# KeyBoy.net
KiCad netlist of a schematic drawn in EAGLE
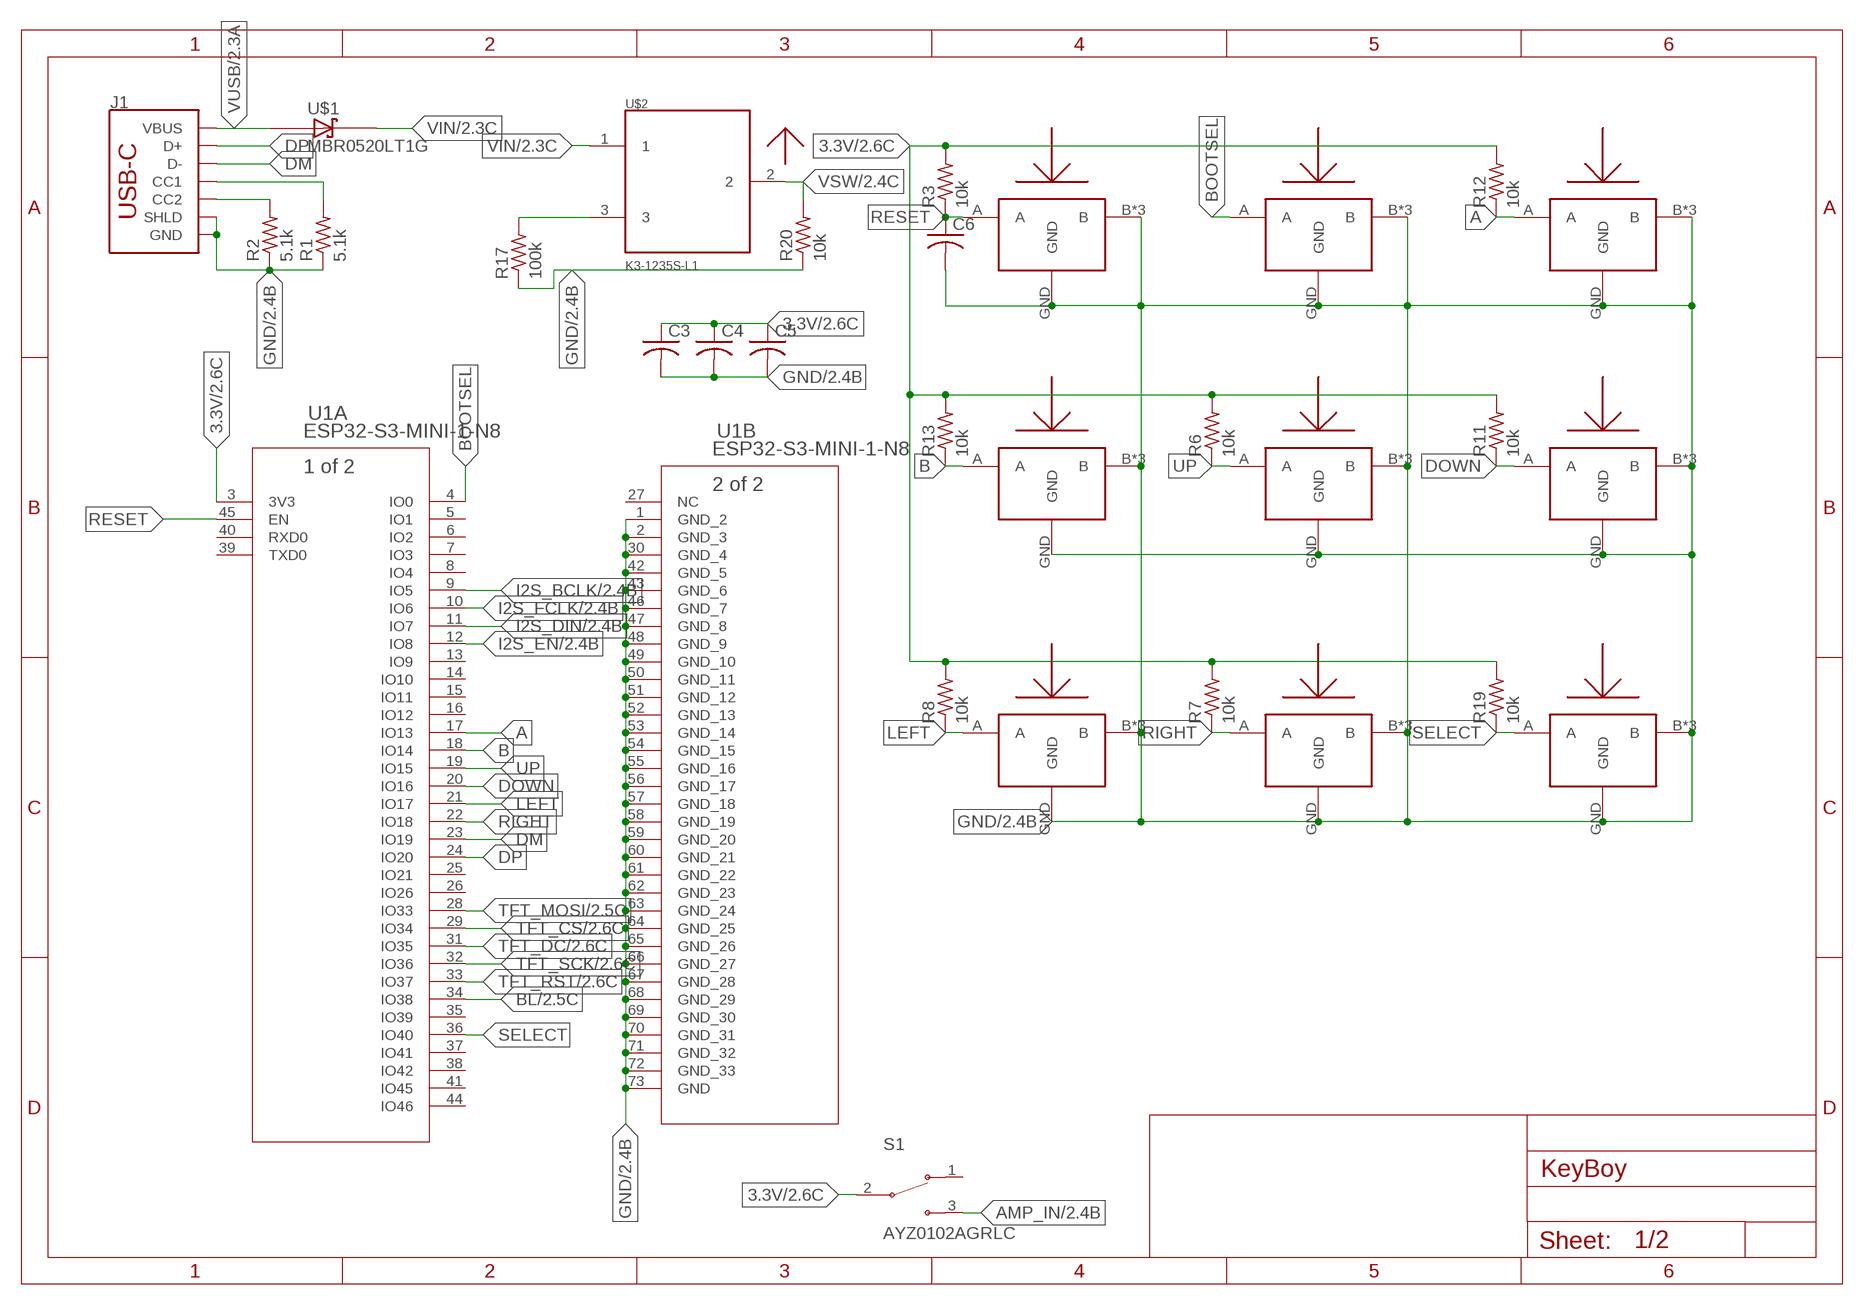
[diagram p0: schematic, sheet 1]
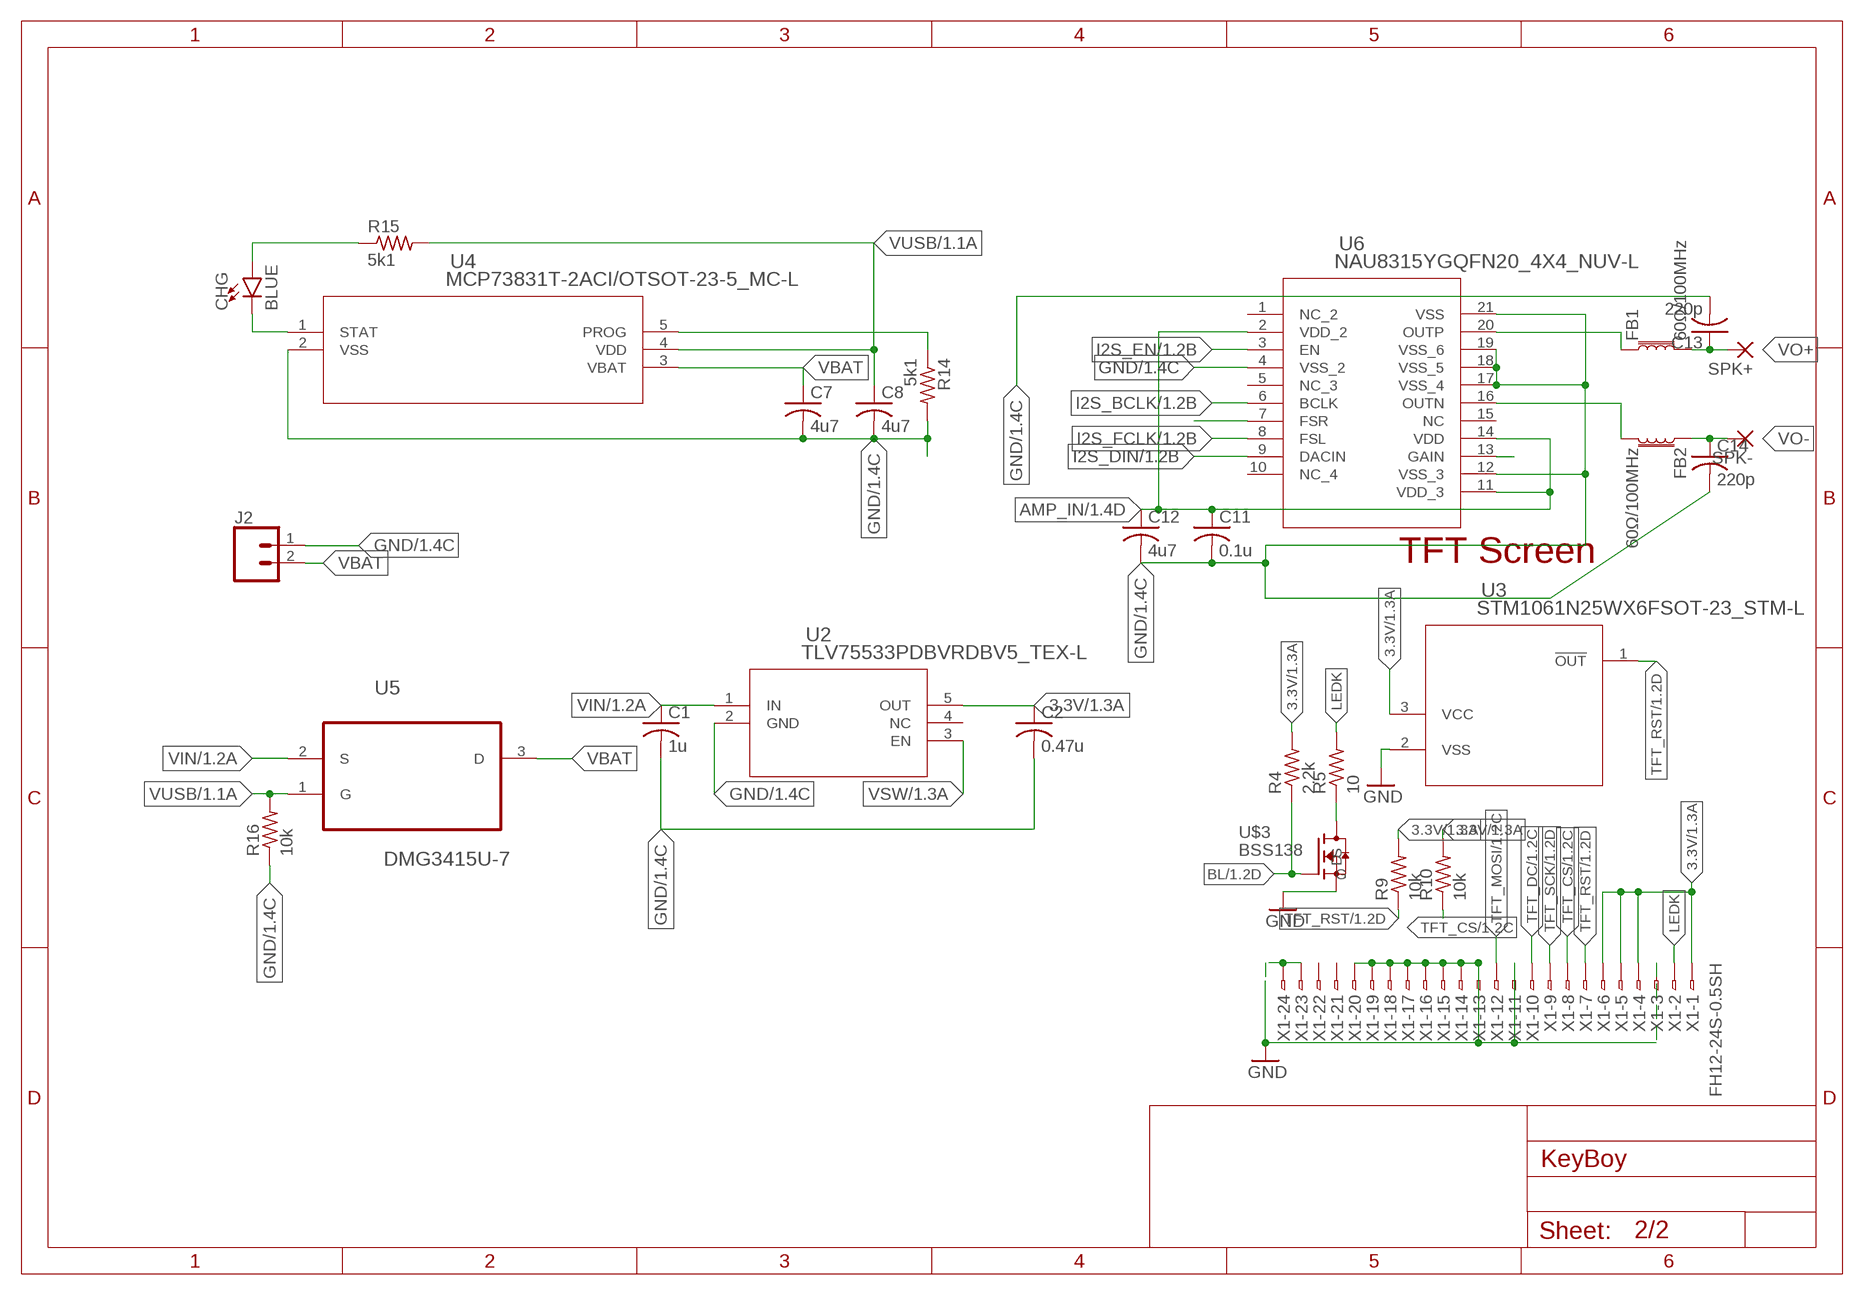
[diagram p1: schematic, sheet 2]

(export (version "E")
  (design (tool "Eeschema 10.0.6"))
  (components
    (comp (ref "C1")
      (value "1u")
      (footprint "eagle-import:C0402")
      (libsource (lib "eagle-import") (part "C-USC0402"))
    )
    (comp (ref "C2")
      (value "0.47u")
      (footprint "eagle-import:C0402")
      (libsource (lib "eagle-import") (part "C-USC0402"))
    )
    (comp (ref "C7")
      (value "4u7")
      (footprint "eagle-import:C0603")
      (libsource (lib "eagle-import") (part "C-USC0603"))
    )
    (comp (ref "C8")
      (value "4u7")
      (footprint "eagle-import:C0603")
      (libsource (lib "eagle-import") (part "C-USC0603"))
    )
    (comp (ref "C11")
      (value "0.1u")
      (footprint "eagle-import:C0603")
      (libsource (lib "eagle-import") (part "C-USC0603"))
    )
    (comp (ref "C12")
      (value "4u7")
      (footprint "eagle-import:C0603")
      (libsource (lib "eagle-import") (part "C-USC0603"))
    )
    (comp (ref "C13")
      (value "220p")
      (footprint "eagle-import:C0603")
      (libsource (lib "eagle-import") (part "C-USC0603"))
    )
    (comp (ref "C14")
      (value "220p")
      (footprint "eagle-import:C0603")
      (libsource (lib "eagle-import") (part "C-USC0603"))
    )
    (comp (ref "CHG")
      (value "BLUE")
      (footprint "eagle-import:LED-0603")
      (libsource (lib "eagle-import") (part "LED0603"))
    )
    (comp (ref "FB1")
      (value "60Ω/100MHz")
      (footprint "eagle-import:0603")
      (libsource (lib "eagle-import") (part "FERRITE_BEAD-0603"))
    )
    (comp (ref "FB2")
      (value "60Ω/100MHz")
      (footprint "eagle-import:0603")
      (libsource (lib "eagle-import") (part "FERRITE_BEAD-0603"))
    )
    (comp (ref "J2")
      (value "CONN_02-JST-2MM-SMT")
      (footprint "eagle-import:JST-2-SMD")
      (libsource (lib "eagle-import") (part "CONN_02-JST-2MM-SMT"))
    )
    (comp (ref "R4")
      (value "2.2k")
      (footprint "eagle-import:R0603")
      (libsource (lib "eagle-import") (part "R-US_R0603"))
    )
    (comp (ref "R5")
      (value "10")
      (footprint "eagle-import:R0402")
      (libsource (lib "eagle-import") (part "R-US_R0402"))
    )
    (comp (ref "R9")
      (value "10k")
      (footprint "eagle-import:R0402")
      (libsource (lib "eagle-import") (part "R-US_R0402"))
    )
    (comp (ref "R10")
      (value "10k")
      (footprint "eagle-import:R0402")
      (libsource (lib "eagle-import") (part "R-US_R0402"))
    )
    (comp (ref "R14")
      (value "5k1")
      (footprint "eagle-import:R0603")
      (libsource (lib "eagle-import") (part "R-US_R0603"))
    )
    (comp (ref "R15")
      (value "5k1")
      (footprint "eagle-import:R0603")
      (libsource (lib "eagle-import") (part "R-US_R0603"))
    )
    (comp (ref "R16")
      (value "10k")
      (footprint "eagle-import:R0402")
      (libsource (lib "eagle-import") (part "R-US_R0402"))
    )
    (comp (ref "SPK+")
      (value "SMD5")
      (footprint "eagle-import:SMD2,54-5,08")
      (libsource (lib "eagle-import") (part "SMD5"))
    )
    (comp (ref "SPK-")
      (value "SMD5")
      (footprint "eagle-import:SMD2,54-5,08")
      (libsource (lib "eagle-import") (part "SMD5"))
    )
    (comp (ref "U$3")
      (value "BSS138")
      (footprint "eagle-import:BSS138")
      (fields (field (name "MF") "MICROSS/On Semiconductor"))
      (libsource (lib "eagle-import") (part "BSS138"))
    )
    (comp (ref "U2")
      (value "TLV75533PDBVRDBV5_TEX-L")
      (footprint "eagle-import:DBV5_TEX-L")
      (fields
        (field (name "MANUFACTURER_PART_NUMBER") "TLV75533PDBVR")
        (field (name "COPYRIGHT") "Copyright (C) 2018 Accelerated Designs. All rights reserved")
      )
      (libsource (lib "eagle-import") (part "TLV75533PDBVRDBV5_TEX-L"))
    )
    (comp (ref "U3")
      (value "STM1061N25WX6FSOT-23_STM-L")
      (footprint "eagle-import:SOT-23_STM-L")
      (fields
        (field (name "MANUFACTURER_PART_NUMBER") "STM1061N25WX6F")
        (field (name "COPYRIGHT") "Copyright (C) 2021 Ultra Librarian. All rights reserved.")
      )
      (libsource (lib "eagle-import") (part "STM1061N25WX6FSOT-23_STM-L"))
    )
    (comp (ref "U4")
      (value "MCP73831T-2ACI/OTSOT-23-5_MC-L")
      (footprint "eagle-import:SOT-23-5_MC-L")
      (fields (field (name "MANUFACTURER_PART_NUMBER") "MCP73831T-2ACI/OT"))
      (libsource (lib "eagle-import") (part "MCP73831T-2ACI/OTSOT-23-5_MC-L"))
    )
    (comp (ref "U5")
      (value "DMG3415U-7")
      (footprint "eagle-import:SOT95P240X105-3N")
      (fields (field (name "MF") "Diodes Inc."))
      (libsource (lib "eagle-import") (part "DMG3415U-7"))
    )
    (comp (ref "U6")
      (value "NAU8315YGQFN20_4X4_NUV-L")
      (footprint "eagle-import:QFN20_4X4_NUV-L")
      (fields
        (field (name "MANUFACTURER_PART_NUMBER") "NAU8315YG")
        (field (name "COPYRIGHT") "Copyright (C) 2023 Ultra Librarian. All rights reserved.")
      )
      (libsource (lib "eagle-import") (part "NAU8315YGQFN20_4X4_NUV-L"))
    )
    (comp (ref "X1")
      (value "FH12-24S-0.5SH")
      (footprint "eagle-import:FH12-24S-0.5SH")
      (fields (field (name "MPN") "FH12-24S-0.5SH(55)"))
      (libsource (lib "eagle-import") (part "FH12-24S-0.5SH"))
    )
    (comp (ref "A")
      (value "SOF-232HST")
      (footprint "eagle-import:3.3X2.9")
      (libsource (lib "eagle-import") (part "SOF-232HST"))
    )
    (comp (ref "B")
      (value "SOF-232HST")
      (footprint "eagle-import:3.3X2.9")
      (libsource (lib "eagle-import") (part "SOF-232HST"))
    )
    (comp (ref "BOOTSEL")
      (value "SOF-232HST")
      (footprint "eagle-import:3.3X2.9")
      (libsource (lib "eagle-import") (part "SOF-232HST"))
    )
    (comp (ref "C3")
      (value "C-USC0402")
      (footprint "eagle-import:C0402")
      (libsource (lib "eagle-import") (part "C-USC0402"))
    )
    (comp (ref "C4")
      (value "C-USC0402")
      (footprint "eagle-import:C0402")
      (libsource (lib "eagle-import") (part "C-USC0402"))
    )
    (comp (ref "C5")
      (value "C-USC0402")
      (footprint "eagle-import:C0402")
      (libsource (lib "eagle-import") (part "C-USC0402"))
    )
    (comp (ref "C6")
      (value "C-USC0402")
      (footprint "eagle-import:C0402")
      (libsource (lib "eagle-import") (part "C-USC0402"))
    )
    (comp (ref "DOWN")
      (value "SOF-232HST")
      (footprint "eagle-import:3.3X2.9")
      (libsource (lib "eagle-import") (part "SOF-232HST"))
    )
    (comp (ref "J1")
      (value "USB_C_2-LAYER_PADS")
      (footprint "eagle-import:USB-C-16P-2LAYER-PADS")
      (libsource (lib "eagle-import") (part "USB_C_2-LAYER_PADS"))
    )
    (comp (ref "LEFT")
      (value "SOF-232HST")
      (footprint "eagle-import:3.3X2.9")
      (libsource (lib "eagle-import") (part "SOF-232HST"))
    )
    (comp (ref "R1")
      (value "5.1k")
      (footprint "eagle-import:R0402")
      (libsource (lib "eagle-import") (part "R-US_R0402"))
    )
    (comp (ref "R2")
      (value "5.1k")
      (footprint "eagle-import:R0402")
      (libsource (lib "eagle-import") (part "R-US_R0402"))
    )
    (comp (ref "R3")
      (value "10k")
      (footprint "eagle-import:R0402")
      (libsource (lib "eagle-import") (part "R-US_R0402"))
    )
    (comp (ref "R6")
      (value "10k")
      (footprint "eagle-import:R0402")
      (libsource (lib "eagle-import") (part "R-US_R0402"))
    )
    (comp (ref "R7")
      (value "10k")
      (footprint "eagle-import:R0402")
      (libsource (lib "eagle-import") (part "R-US_R0402"))
    )
    (comp (ref "R8")
      (value "10k")
      (footprint "eagle-import:R0402")
      (libsource (lib "eagle-import") (part "R-US_R0402"))
    )
    (comp (ref "R11")
      (value "10k")
      (footprint "eagle-import:R0402")
      (libsource (lib "eagle-import") (part "R-US_R0402"))
    )
    (comp (ref "R12")
      (value "10k")
      (footprint "eagle-import:R0402")
      (libsource (lib "eagle-import") (part "R-US_R0402"))
    )
    (comp (ref "R13")
      (value "10k")
      (footprint "eagle-import:R0402")
      (libsource (lib "eagle-import") (part "R-US_R0402"))
    )
    (comp (ref "R17")
      (value "100k")
      (footprint "eagle-import:R0402")
      (libsource (lib "eagle-import") (part "R-US_R0402"))
    )
    (comp (ref "R19")
      (value "10k")
      (footprint "eagle-import:R0402")
      (libsource (lib "eagle-import") (part "R-US_R0402"))
    )
    (comp (ref "R20")
      (value "10k")
      (footprint "eagle-import:R0402")
      (libsource (lib "eagle-import") (part "R-US_R0402"))
    )
    (comp (ref "RESET")
      (value "SOF-232HST")
      (footprint "eagle-import:3.3X2.9")
      (libsource (lib "eagle-import") (part "SOF-232HST"))
    )
    (comp (ref "RIGHT")
      (value "SOF-232HST")
      (footprint "eagle-import:3.3X2.9")
      (libsource (lib "eagle-import") (part "SOF-232HST"))
    )
    (comp (ref "S1")
      (value "AYZ0102AGRLC")
      (footprint "eagle-import:SW_AYZ0102AGRLC")
      (fields (field (name "MF") "C&K"))
      (libsource (lib "eagle-import") (part "AYZ0102AGRLC"))
    )
    (comp (ref "SELECT")
      (value "SOF-232HST")
      (footprint "eagle-import:3.3X2.9")
      (libsource (lib "eagle-import") (part "SOF-232HST"))
    )
    (comp (ref "U$1")
      (value "MBR0520LT1G")
      (footprint "eagle-import:SOD3716X117(SOD-123)")
      (fields (field (name "MF") "ON Semiconductor"))
      (libsource (lib "eagle-import") (part "MBR0520LT1G"))
    )
    (comp (ref "U$2")
      (value "K3-1235S-L1")
      (footprint "eagle-import:K3-1235S-L1")
      (libsource (lib "eagle-import") (part "K3-1235S-L1"))
    )
    (comp (ref "U1")
      (value "ESP32-S3-MINI-1-N8")
      (footprint "eagle-import:ESP32-S2-MINI-1-N4_EXP")
      (fields
        (field (name "MANUFACTURER_PART_NUMBER") "ESP32-S2-MINI-1-N4")
        (field (name "COPYRIGHT") "Copyright (C) 2021 Ultra Librarian. All rights reserved.")
      )
      (libsource (lib "eagle-import") (part "ESP32-S2-MINI-1-N4"))
    )
    (comp (ref "UP")
      (value "SOF-232HST")
      (footprint "eagle-import:3.3X2.9")
      (libsource (lib "eagle-import") (part "SOF-232HST"))
    )
  )
  (nets
    (net (code "1") (name "3.3V") (class "Default")
      (node (ref "C2") (pin "1") (pinfunction "1_1") (pintype "passive"))
      (node (ref "C3") (pin "1") (pinfunction "1_1") (pintype "passive"))
      (node (ref "C4") (pin "1") (pinfunction "1_1") (pintype "passive"))
      (node (ref "C5") (pin "1") (pinfunction "1_1") (pintype "passive"))
      (node (ref "R10") (pin "2") (pinfunction "2_2") (pintype "passive"))
      (node (ref "R11") (pin "2") (pinfunction "2_2") (pintype "passive"))
      (node (ref "R12") (pin "2") (pinfunction "2_2") (pintype "passive"))
      (node (ref "R13") (pin "2") (pinfunction "2_2") (pintype "passive"))
      (node (ref "R19") (pin "2") (pinfunction "2_2") (pintype "passive"))
      (node (ref "R3") (pin "2") (pinfunction "2_2") (pintype "passive"))
      (node (ref "R4") (pin "2") (pinfunction "2_2") (pintype "passive"))
      (node (ref "R6") (pin "2") (pinfunction "2_2") (pintype "passive"))
      (node (ref "R7") (pin "2") (pinfunction "2_2") (pintype "passive"))
      (node (ref "R8") (pin "2") (pinfunction "2_2") (pintype "passive"))
      (node (ref "R9") (pin "2") (pinfunction "2_2") (pintype "passive"))
      (node (ref "S1") (pin "2") (pinfunction "2_2") (pintype "passive"))
      (node (ref "U1") (pin "3") (pinfunction "3V3_3") (pintype "passive"))
      (node (ref "U2") (pin "5") (pinfunction "OUT_5") (pintype "output"))
      (node (ref "U3") (pin "3") (pinfunction "VCC_3") (pintype "power_in"))
      (node (ref "X1") (pin "1") (pinfunction "1_1") (pintype "passive"))
      (node (ref "X1") (pin "4") (pinfunction "1_4") (pintype "passive"))
      (node (ref "X1") (pin "5") (pinfunction "1_5") (pintype "passive"))
      (node (ref "X1") (pin "6") (pinfunction "1_6") (pintype "passive"))
    )
    (net (code "2") (name "A") (class "Default")
      (node (ref "A") (pin "A") (pinfunction "A_A") (pintype "bidirectional"))
      (node (ref "R12") (pin "1") (pinfunction "1_1") (pintype "passive"))
      (node (ref "U1") (pin "17") (pinfunction "IO13_17") (pintype "bidirectional"))
    )
    (net (code "3") (name "AMP_IN") (class "Default")
      (node (ref "C11") (pin "1") (pinfunction "1_1") (pintype "passive"))
      (node (ref "C12") (pin "1") (pinfunction "1_1") (pintype "passive"))
      (node (ref "S1") (pin "3") (pinfunction "3_3") (pintype "passive"))
      (node (ref "U6") (pin "11") (pinfunction "VDD_3_11") (pintype "power_in"))
      (node (ref "U6") (pin "14") (pinfunction "VDD_14") (pintype "power_in"))
      (node (ref "U6") (pin "2") (pinfunction "VDD_2_2") (pintype "power_in"))
    )
    (net (code "4") (name "B") (class "Default")
      (node (ref "B") (pin "A") (pinfunction "A_A") (pintype "bidirectional"))
      (node (ref "R13") (pin "1") (pinfunction "1_1") (pintype "passive"))
      (node (ref "U1") (pin "18") (pinfunction "IO14_18") (pintype "bidirectional"))
    )
    (net (code "5") (name "BL") (class "Default")
      (node (ref "R4") (pin "1") (pinfunction "1_1") (pintype "passive"))
      (node (ref "U$3") (pin "G") (pinfunction "G_G") (pintype "passive"))
      (node (ref "U1") (pin "34") (pinfunction "IO38_34") (pintype "bidirectional"))
    )
    (net (code "6") (name "BOOTSEL") (class "Default")
      (node (ref "BOOTSEL") (pin "A") (pinfunction "A_A") (pintype "bidirectional"))
      (node (ref "U1") (pin "4") (pinfunction "IO0_4") (pintype "bidirectional"))
    )
    (net (code "7") (name "DM") (class "Default")
      (node (ref "J1") (pin "A7") (pinfunction "D-_A7") (pintype "bidirectional"))
      (node (ref "J1") (pin "B7") (pinfunction "D-_B7") (pintype "bidirectional"))
      (node (ref "U1") (pin "23") (pinfunction "IO19_23") (pintype "bidirectional"))
    )
    (net (code "8") (name "DOWN") (class "Default")
      (node (ref "DOWN") (pin "A") (pinfunction "A_A") (pintype "bidirectional"))
      (node (ref "R11") (pin "1") (pinfunction "1_1") (pintype "passive"))
      (node (ref "U1") (pin "20") (pinfunction "IO16_20") (pintype "bidirectional"))
    )
    (net (code "9") (name "DP") (class "Default")
      (node (ref "J1") (pin "A6") (pinfunction "D+_A6") (pintype "bidirectional"))
      (node (ref "J1") (pin "B6") (pinfunction "D+_B6") (pintype "bidirectional"))
      (node (ref "U1") (pin "24") (pinfunction "IO20_24") (pintype "bidirectional"))
    )
    (net (code "10") (name "GND") (class "Default")
      (node (ref "A") (pin "B") (pinfunction "B_B") (pintype "bidirectional"))
      (node (ref "A") (pin "B2") (pinfunction "B_B2") (pintype "bidirectional"))
      (node (ref "A") (pin "B3") (pinfunction "B_B3") (pintype "bidirectional"))
      (node (ref "A") (pin "GND") (pinfunction "GND_GND") (pintype "bidirectional"))
      (node (ref "B") (pin "B") (pinfunction "B_B") (pintype "bidirectional"))
      (node (ref "B") (pin "B2") (pinfunction "B_B2") (pintype "bidirectional"))
      (node (ref "B") (pin "B3") (pinfunction "B_B3") (pintype "bidirectional"))
      (node (ref "B") (pin "GND") (pinfunction "GND_GND") (pintype "bidirectional"))
      (node (ref "BOOTSEL") (pin "B") (pinfunction "B_B") (pintype "bidirectional"))
      (node (ref "BOOTSEL") (pin "B2") (pinfunction "B_B2") (pintype "bidirectional"))
      (node (ref "BOOTSEL") (pin "B3") (pinfunction "B_B3") (pintype "bidirectional"))
      (node (ref "BOOTSEL") (pin "GND") (pinfunction "GND_GND") (pintype "bidirectional"))
      (node (ref "C1") (pin "2") (pinfunction "2_2") (pintype "passive"))
      (node (ref "C11") (pin "2") (pinfunction "2_2") (pintype "passive"))
      (node (ref "C12") (pin "2") (pinfunction "2_2") (pintype "passive"))
      (node (ref "C13") (pin "2") (pinfunction "2_2") (pintype "passive"))
      (node (ref "C14") (pin "2") (pinfunction "2_2") (pintype "passive"))
      (node (ref "C2") (pin "2") (pinfunction "2_2") (pintype "passive"))
      (node (ref "C3") (pin "2") (pinfunction "2_2") (pintype "passive"))
      (node (ref "C4") (pin "2") (pinfunction "2_2") (pintype "passive"))
      (node (ref "C5") (pin "2") (pinfunction "2_2") (pintype "passive"))
      (node (ref "C6") (pin "2") (pinfunction "2_2") (pintype "passive"))
      (node (ref "C7") (pin "2") (pinfunction "2_2") (pintype "passive"))
      (node (ref "C8") (pin "2") (pinfunction "2_2") (pintype "passive"))
      (node (ref "DOWN") (pin "B") (pinfunction "B_B") (pintype "bidirectional"))
      (node (ref "DOWN") (pin "B2") (pinfunction "B_B2") (pintype "bidirectional"))
      (node (ref "DOWN") (pin "B3") (pinfunction "B_B3") (pintype "bidirectional"))
      (node (ref "DOWN") (pin "GND") (pinfunction "GND_GND") (pintype "bidirectional"))
      (node (ref "J1") (pin "GND") (pinfunction "GND_GND") (pintype "bidirectional"))
      (node (ref "J1") (pin "GND2") (pinfunction "GND_GND2") (pintype "bidirectional"))
      (node (ref "J1") (pin "P$1") (pinfunction "SHLD_P$1") (pintype "bidirectional"))
      (node (ref "J1") (pin "P$2") (pinfunction "SHLD_P$2") (pintype "bidirectional"))
      (node (ref "J1") (pin "P$3") (pinfunction "SHLD_P$3") (pintype "bidirectional"))
      (node (ref "J1") (pin "P$4") (pinfunction "SHLD_P$4") (pintype "bidirectional"))
      (node (ref "J1") (pin "SHLD1") (pinfunction "SHLD_SHLD1") (pintype "bidirectional"))
      (node (ref "J1") (pin "SHLD2") (pinfunction "SHLD_SHLD2") (pintype "bidirectional"))
      (node (ref "J1") (pin "SHLD3") (pinfunction "SHLD_SHLD3") (pintype "bidirectional"))
      (node (ref "J1") (pin "SHLD4") (pinfunction "SHLD_SHLD4") (pintype "bidirectional"))
      (node (ref "J2") (pin "1") (pinfunction "2_1") (pintype "passive"))
      (node (ref "LEFT") (pin "B") (pinfunction "B_B") (pintype "bidirectional"))
      (node (ref "LEFT") (pin "B2") (pinfunction "B_B2") (pintype "bidirectional"))
      (node (ref "LEFT") (pin "B3") (pinfunction "B_B3") (pintype "bidirectional"))
      (node (ref "LEFT") (pin "GND") (pinfunction "GND_GND") (pintype "bidirectional"))
      (node (ref "R1") (pin "1") (pinfunction "1_1") (pintype "passive"))
      (node (ref "R14") (pin "2") (pinfunction "2_2") (pintype "passive"))
      (node (ref "R16") (pin "1") (pinfunction "1_1") (pintype "passive"))
      (node (ref "R17") (pin "1") (pinfunction "1_1") (pintype "passive"))
      (node (ref "R2") (pin "1") (pinfunction "1_1") (pintype "passive"))
      (node (ref "R20") (pin "1") (pinfunction "1_1") (pintype "passive"))
      (node (ref "RESET") (pin "B") (pinfunction "B_B") (pintype "bidirectional"))
      (node (ref "RESET") (pin "B2") (pinfunction "B_B2") (pintype "bidirectional"))
      (node (ref "RESET") (pin "B3") (pinfunction "B_B3") (pintype "bidirectional"))
      (node (ref "RESET") (pin "GND") (pinfunction "GND_GND") (pintype "bidirectional"))
      (node (ref "RIGHT") (pin "B") (pinfunction "B_B") (pintype "bidirectional"))
      (node (ref "RIGHT") (pin "B2") (pinfunction "B_B2") (pintype "bidirectional"))
      (node (ref "RIGHT") (pin "B3") (pinfunction "B_B3") (pintype "bidirectional"))
      (node (ref "RIGHT") (pin "GND") (pinfunction "GND_GND") (pintype "bidirectional"))
      (node (ref "SELECT") (pin "B") (pinfunction "B_B") (pintype "bidirectional"))
      (node (ref "SELECT") (pin "B2") (pinfunction "B_B2") (pintype "bidirectional"))
      (node (ref "SELECT") (pin "B3") (pinfunction "B_B3") (pintype "bidirectional"))
      (node (ref "SELECT") (pin "GND") (pinfunction "GND_GND") (pintype "bidirectional"))
      (node (ref "U$3") (pin "S") (pinfunction "S_S") (pintype "passive"))
      (node (ref "U1") (pin "1") (pinfunction "GND_2_1") (pintype "passive"))
      (node (ref "U1") (pin "2") (pinfunction "GND_3_2") (pintype "passive"))
      (node (ref "U1") (pin "30") (pinfunction "GND_4_30") (pintype "passive"))
      (node (ref "U1") (pin "42") (pinfunction "GND_5_42") (pintype "passive"))
      (node (ref "U1") (pin "43") (pinfunction "GND_6_43") (pintype "passive"))
      (node (ref "U1") (pin "46") (pinfunction "GND_7_46") (pintype "passive"))
      (node (ref "U1") (pin "47") (pinfunction "GND_8_47") (pintype "passive"))
      (node (ref "U1") (pin "48") (pinfunction "GND_9_48") (pintype "passive"))
      (node (ref "U1") (pin "49") (pinfunction "GND_10_49") (pintype "passive"))
      (node (ref "U1") (pin "50") (pinfunction "GND_11_50") (pintype "passive"))
      (node (ref "U1") (pin "51") (pinfunction "GND_12_51") (pintype "passive"))
      (node (ref "U1") (pin "52") (pinfunction "GND_13_52") (pintype "passive"))
      (node (ref "U1") (pin "53") (pinfunction "GND_14_53") (pintype "passive"))
      (node (ref "U1") (pin "54") (pinfunction "GND_15_54") (pintype "passive"))
      (node (ref "U1") (pin "55") (pinfunction "GND_16_55") (pintype "passive"))
      (node (ref "U1") (pin "56") (pinfunction "GND_17_56") (pintype "passive"))
      (node (ref "U1") (pin "57") (pinfunction "GND_18_57") (pintype "passive"))
      (node (ref "U1") (pin "58") (pinfunction "GND_19_58") (pintype "passive"))
      (node (ref "U1") (pin "59") (pinfunction "GND_20_59") (pintype "passive"))
      (node (ref "U1") (pin "60") (pinfunction "GND_21_60") (pintype "passive"))
      (node (ref "U1") (pin "61") (pinfunction "GND_22_61") (pintype "passive"))
      (node (ref "U1") (pin "62") (pinfunction "GND_23_62") (pintype "passive"))
      (node (ref "U1") (pin "63") (pinfunction "GND_24_63") (pintype "passive"))
      (node (ref "U1") (pin "64") (pinfunction "GND_25_64") (pintype "passive"))
      (node (ref "U1") (pin "65") (pinfunction "GND_26_65") (pintype "passive"))
      (node (ref "U1") (pin "66") (pinfunction "GND_27_66") (pintype "passive"))
      (node (ref "U1") (pin "67") (pinfunction "GND_28_67") (pintype "passive"))
      (node (ref "U1") (pin "68") (pinfunction "GND_29_68") (pintype "passive"))
      (node (ref "U1") (pin "69") (pinfunction "GND_30_69") (pintype "passive"))
      (node (ref "U1") (pin "70") (pinfunction "GND_31_70") (pintype "passive"))
      (node (ref "U1") (pin "71") (pinfunction "GND_32_71") (pintype "passive"))
      (node (ref "U1") (pin "72") (pinfunction "GND_33_72") (pintype "passive"))
      (node (ref "U1") (pin "73") (pinfunction "GND_73") (pintype "passive"))
      (node (ref "U2") (pin "2") (pinfunction "GND_2") (pintype "power_in"))
      (node (ref "U3") (pin "2") (pinfunction "VSS_2") (pintype "power_in"))
      (node (ref "U4") (pin "2") (pinfunction "VSS_2") (pintype "passive"))
      (node (ref "U6") (pin "12") (pinfunction "VSS_3_12") (pintype "passive"))
      (node (ref "U6") (pin "17") (pinfunction "VSS_4_17") (pintype "passive"))
      (node (ref "U6") (pin "18") (pinfunction "VSS_5_18") (pintype "passive"))
      (node (ref "U6") (pin "19") (pinfunction "VSS_6_19") (pintype "passive"))
      (node (ref "U6") (pin "21") (pinfunction "VSS_21") (pintype "passive"))
      (node (ref "U6") (pin "4") (pinfunction "VSS_2_4") (pintype "passive"))
      (node (ref "UP") (pin "B") (pinfunction "B_B") (pintype "bidirectional"))
      (node (ref "UP") (pin "B2") (pinfunction "B_B2") (pintype "bidirectional"))
      (node (ref "UP") (pin "B3") (pinfunction "B_B3") (pintype "bidirectional"))
      (node (ref "UP") (pin "GND") (pinfunction "GND_GND") (pintype "bidirectional"))
      (node (ref "X1") (pin "11") (pinfunction "1_11") (pintype "passive"))
      (node (ref "X1") (pin "13") (pinfunction "1_13") (pintype "passive"))
      (node (ref "X1") (pin "14") (pinfunction "1_14") (pintype "passive"))
      (node (ref "X1") (pin "15") (pinfunction "1_15") (pintype "passive"))
      (node (ref "X1") (pin "16") (pinfunction "1_16") (pintype "passive"))
      (node (ref "X1") (pin "17") (pinfunction "1_17") (pintype "passive"))
      (node (ref "X1") (pin "18") (pinfunction "1_18") (pintype "passive"))
      (node (ref "X1") (pin "19") (pinfunction "1_19") (pintype "passive"))
      (node (ref "X1") (pin "20") (pinfunction "1_20") (pintype "passive"))
      (node (ref "X1") (pin "23") (pinfunction "1_23") (pintype "passive"))
      (node (ref "X1") (pin "24") (pinfunction "1_24") (pintype "passive"))
      (node (ref "X1") (pin "3") (pinfunction "1_3") (pintype "passive"))
    )
    (net (code "11") (name "I2S_BCLK") (class "Default")
      (node (ref "U1") (pin "9") (pinfunction "IO5_9") (pintype "bidirectional"))
      (node (ref "U6") (pin "6") (pinfunction "BCLK_6") (pintype "input"))
    )
    (net (code "12") (name "I2S_DIN") (class "Default")
      (node (ref "U1") (pin "11") (pinfunction "IO7_11") (pintype "bidirectional"))
      (node (ref "U6") (pin "9") (pinfunction "DACIN_9") (pintype "input"))
    )
    (net (code "13") (name "I2S_EN") (class "Default")
      (node (ref "U1") (pin "12") (pinfunction "IO8_12") (pintype "bidirectional"))
      (node (ref "U6") (pin "3") (pinfunction "EN_3") (pintype "input"))
    )
    (net (code "14") (name "I2S_FCLK") (class "Default")
      (node (ref "U1") (pin "10") (pinfunction "IO6_10") (pintype "bidirectional"))
      (node (ref "U6") (pin "8") (pinfunction "FSL_8") (pintype "input"))
    )
    (net (code "15") (name "LEDK") (class "Default")
      (node (ref "R5") (pin "2") (pinfunction "2_2") (pintype "passive"))
      (node (ref "X1") (pin "2") (pinfunction "1_2") (pintype "passive"))
    )
    (net (code "16") (name "LEFT") (class "Default")
      (node (ref "LEFT") (pin "A") (pinfunction "A_A") (pintype "bidirectional"))
      (node (ref "R8") (pin "1") (pinfunction "1_1") (pintype "passive"))
      (node (ref "U1") (pin "21") (pinfunction "IO17_21") (pintype "bidirectional"))
    )
    (net (code "17") (name "Net-(CHG-PadA)") (class "Default")
      (node (ref "CHG") (pin "A") (pinfunction "A_A") (pintype "passive"))
      (node (ref "R15") (pin "1") (pinfunction "1_1") (pintype "passive"))
    )
    (net (code "18") (name "Net-(J1-CC1)") (class "Default")
      (node (ref "J1") (pin "A5") (pinfunction "CC1_A5") (pintype "bidirectional"))
      (node (ref "R1") (pin "2") (pinfunction "2_2") (pintype "passive"))
    )
    (net (code "19") (name "Net-(J1-CC2)") (class "Default")
      (node (ref "J1") (pin "B5") (pinfunction "CC2_B5") (pintype "bidirectional"))
      (node (ref "R2") (pin "2") (pinfunction "2_2") (pintype "passive"))
    )
    (net (code "20") (name "Net-(R5-Pad1)") (class "Default")
      (node (ref "R5") (pin "1") (pinfunction "1_1") (pintype "passive"))
      (node (ref "U$3") (pin "D") (pinfunction "D_D") (pintype "passive"))
    )
    (net (code "21") (name "Net-(R17-Pad2)") (class "Default")
      (node (ref "R17") (pin "2") (pinfunction "2_2") (pintype "passive"))
      (node (ref "U$2") (pin "3") (pinfunction "3_3") (pintype "bidirectional"))
    )
    (net (code "22") (name "Net-(U4-PROG)") (class "Default")
      (node (ref "R14") (pin "1") (pinfunction "1_1") (pintype "passive"))
      (node (ref "U4") (pin "5") (pinfunction "PROG_5") (pintype "passive"))
    )
    (net (code "23") (name "Net-(U4-STAT)") (class "Default")
      (node (ref "CHG") (pin "C") (pinfunction "C_C") (pintype "passive"))
      (node (ref "U4") (pin "1") (pinfunction "STAT_1") (pintype "passive"))
    )
    (net (code "24") (name "Net-(U6-OUTN)") (class "Default")
      (node (ref "FB2") (pin "2") (pinfunction "2_2") (pintype "passive"))
      (node (ref "U6") (pin "16") (pinfunction "OUTN_16") (pintype "passive"))
    )
    (net (code "25") (name "Net-(U6-OUTP)") (class "Default")
      (node (ref "FB1") (pin "1") (pinfunction "1_1") (pintype "passive"))
      (node (ref "U6") (pin "20") (pinfunction "OUTP_20") (pintype "passive"))
    )
    (net (code "26") (name "RESET") (class "Default")
      (node (ref "C6") (pin "1") (pinfunction "1_1") (pintype "passive"))
      (node (ref "R3") (pin "1") (pinfunction "1_1") (pintype "passive"))
      (node (ref "RESET") (pin "A") (pinfunction "A_A") (pintype "bidirectional"))
      (node (ref "U1") (pin "45") (pinfunction "EN_45") (pintype "passive"))
    )
    (net (code "27") (name "RIGHT") (class "Default")
      (node (ref "R7") (pin "1") (pinfunction "1_1") (pintype "passive"))
      (node (ref "RIGHT") (pin "A") (pinfunction "A_A") (pintype "bidirectional"))
      (node (ref "U1") (pin "22") (pinfunction "IO18_22") (pintype "bidirectional"))
    )
    (net (code "28") (name "SELECT") (class "Default")
      (node (ref "R19") (pin "1") (pinfunction "1_1") (pintype "passive"))
      (node (ref "SELECT") (pin "A") (pinfunction "A_A") (pintype "bidirectional"))
      (node (ref "U1") (pin "36") (pinfunction "IO40_36") (pintype "bidirectional"))
    )
    (net (code "29") (name "TFT_CS") (class "Default")
      (node (ref "R10") (pin "1") (pinfunction "1_1") (pintype "passive"))
      (node (ref "U1") (pin "29") (pinfunction "IO34_29") (pintype "bidirectional"))
      (node (ref "X1") (pin "8") (pinfunction "1_8") (pintype "passive"))
    )
    (net (code "30") (name "TFT_DC") (class "Default")
      (node (ref "U1") (pin "31") (pinfunction "IO35_31") (pintype "bidirectional"))
      (node (ref "X1") (pin "10") (pinfunction "1_10") (pintype "passive"))
    )
    (net (code "31") (name "TFT_MOSI") (class "Default")
      (node (ref "U1") (pin "28") (pinfunction "IO33_28") (pintype "bidirectional"))
      (node (ref "X1") (pin "12") (pinfunction "1_12") (pintype "passive"))
    )
    (net (code "32") (name "TFT_RST") (class "Default")
      (node (ref "R9") (pin "1") (pinfunction "1_1") (pintype "passive"))
      (node (ref "U1") (pin "33") (pinfunction "IO37_33") (pintype "bidirectional"))
      (node (ref "U3") (pin "1") (pinfunction "~{OUT}_1") (pintype "output"))
      (node (ref "X1") (pin "7") (pinfunction "1_7") (pintype "passive"))
    )
    (net (code "33") (name "TFT_SCK") (class "Default")
      (node (ref "U1") (pin "32") (pinfunction "IO36_32") (pintype "bidirectional"))
      (node (ref "X1") (pin "9") (pinfunction "1_9") (pintype "passive"))
    )
    (net (code "34") (name "UP") (class "Default")
      (node (ref "R6") (pin "1") (pinfunction "1_1") (pintype "passive"))
      (node (ref "U1") (pin "19") (pinfunction "IO15_19") (pintype "bidirectional"))
      (node (ref "UP") (pin "A") (pinfunction "A_A") (pintype "bidirectional"))
    )
    (net (code "35") (name "VBAT") (class "Default")
      (node (ref "C7") (pin "1") (pinfunction "1_1") (pintype "passive"))
      (node (ref "J2") (pin "2") (pinfunction "1_2") (pintype "passive"))
      (node (ref "U4") (pin "3") (pinfunction "VBAT_3") (pintype "passive"))
      (node (ref "U5") (pin "3") (pinfunction "D_3") (pintype "output"))
    )
    (net (code "36") (name "VIN") (class "Default")
      (node (ref "C1") (pin "1") (pinfunction "1_1") (pintype "passive"))
      (node (ref "U$1") (pin "1") (pinfunction "C_1") (pintype "passive"))
      (node (ref "U$2") (pin "1") (pinfunction "1_1") (pintype "bidirectional"))
      (node (ref "U2") (pin "1") (pinfunction "IN_1") (pintype "input"))
      (node (ref "U5") (pin "2") (pinfunction "S_2") (pintype "passive"))
    )
    (net (code "37") (name "VO+") (class "Default")
      (node (ref "C13") (pin "1") (pinfunction "1_1") (pintype "passive"))
      (node (ref "FB1") (pin "2") (pinfunction "2_2") (pintype "passive"))
      (node (ref "SPK+") (pin "1") (pinfunction "P_1") (pintype "passive"))
    )
    (net (code "38") (name "VO-") (class "Default")
      (node (ref "C14") (pin "1") (pinfunction "1_1") (pintype "passive"))
      (node (ref "FB2") (pin "1") (pinfunction "1_1") (pintype "passive"))
      (node (ref "SPK-") (pin "1") (pinfunction "P_1") (pintype "passive"))
    )
    (net (code "39") (name "VSW") (class "Default")
      (node (ref "R20") (pin "2") (pinfunction "2_2") (pintype "passive"))
      (node (ref "U$2") (pin "2") (pinfunction "2_2") (pintype "bidirectional"))
      (node (ref "U2") (pin "3") (pinfunction "EN_3") (pintype "input"))
    )
    (net (code "40") (name "VUSB") (class "Default")
      (node (ref "C8") (pin "1") (pinfunction "1_1") (pintype "passive"))
      (node (ref "J1") (pin "VBUS1") (pinfunction "VBUS_VBUS1") (pintype "bidirectional"))
      (node (ref "J1") (pin "VBUS2") (pinfunction "VBUS_VBUS2") (pintype "bidirectional"))
      (node (ref "R15") (pin "2") (pinfunction "2_2") (pintype "passive"))
      (node (ref "R16") (pin "2") (pinfunction "2_2") (pintype "passive"))
      (node (ref "U$1") (pin "2") (pinfunction "A_2") (pintype "passive"))
      (node (ref "U4") (pin "4") (pinfunction "VDD_4") (pintype "passive"))
      (node (ref "U5") (pin "1") (pinfunction "G_1") (pintype "power_in"))
    )
    (net (code "41") (name "unconnected-(S1-Pad1)") (class "Default")
      (node (ref "S1") (pin "1") (pinfunction "1_1") (pintype "passive"))
    )
    (net (code "42") (name "unconnected-(U1A-IO1-Pad5)") (class "Default")
      (node (ref "U1") (pin "5") (pinfunction "IO1_5") (pintype "bidirectional"))
    )
    (net (code "43") (name "unconnected-(U1A-IO2-Pad6)") (class "Default")
      (node (ref "U1") (pin "6") (pinfunction "IO2_6") (pintype "bidirectional"))
    )
    (net (code "44") (name "unconnected-(U1A-IO3-Pad7)") (class "Default")
      (node (ref "U1") (pin "7") (pinfunction "IO3_7") (pintype "bidirectional"))
    )
    (net (code "45") (name "unconnected-(U1A-IO4-Pad8)") (class "Default")
      (node (ref "U1") (pin "8") (pinfunction "IO4_8") (pintype "bidirectional"))
    )
    (net (code "46") (name "unconnected-(U1A-IO9-Pad13)") (class "Default")
      (node (ref "U1") (pin "13") (pinfunction "IO9_13") (pintype "bidirectional"))
    )
    (net (code "47") (name "unconnected-(U1A-IO10-Pad14)") (class "Default")
      (node (ref "U1") (pin "14") (pinfunction "IO10_14") (pintype "bidirectional"))
    )
    (net (code "48") (name "unconnected-(U1A-IO11-Pad15)") (class "Default")
      (node (ref "U1") (pin "15") (pinfunction "IO11_15") (pintype "bidirectional"))
    )
    (net (code "49") (name "unconnected-(U1A-IO12-Pad16)") (class "Default")
      (node (ref "U1") (pin "16") (pinfunction "IO12_16") (pintype "bidirectional"))
    )
    (net (code "50") (name "unconnected-(U1A-IO21-Pad25)") (class "Default")
      (node (ref "U1") (pin "25") (pinfunction "IO21_25") (pintype "bidirectional"))
    )
    (net (code "51") (name "unconnected-(U1A-IO26-Pad26)") (class "Default")
      (node (ref "U1") (pin "26") (pinfunction "IO26_26") (pintype "bidirectional"))
    )
    (net (code "52") (name "unconnected-(U1A-IO39-Pad35)") (class "Default")
      (node (ref "U1") (pin "35") (pinfunction "IO39_35") (pintype "bidirectional"))
    )
    (net (code "53") (name "unconnected-(U1A-IO41-Pad37)") (class "Default")
      (node (ref "U1") (pin "37") (pinfunction "IO41_37") (pintype "bidirectional"))
    )
    (net (code "54") (name "unconnected-(U1A-IO42-Pad38)") (class "Default")
      (node (ref "U1") (pin "38") (pinfunction "IO42_38") (pintype "bidirectional"))
    )
    (net (code "55") (name "unconnected-(U1A-IO45-Pad41)") (class "Default")
      (node (ref "U1") (pin "41") (pinfunction "IO45_41") (pintype "bidirectional"))
    )
    (net (code "56") (name "unconnected-(U1A-IO46-Pad44)") (class "Default")
      (node (ref "U1") (pin "44") (pinfunction "IO46_44") (pintype "bidirectional"))
    )
    (net (code "57") (name "unconnected-(U1A-RXD0-Pad40)") (class "Default")
      (node (ref "U1") (pin "40") (pinfunction "RXD0_40") (pintype "bidirectional"))
    )
    (net (code "58") (name "unconnected-(U1A-TXD0-Pad39)") (class "Default")
      (node (ref "U1") (pin "39") (pinfunction "TXD0_39") (pintype "bidirectional"))
    )
    (net (code "59") (name "unconnected-(U1B-NC-Pad27)") (class "Default")
      (node (ref "U1") (pin "27") (pinfunction "NC_27") (pintype "no_connect"))
    )
    (net (code "60") (name "unconnected-(U2-NC-Pad4)") (class "Default")
      (node (ref "U2") (pin "4") (pinfunction "NC_4") (pintype "no_connect"))
    )
    (net (code "61") (name "unconnected-(U6-FSR-Pad7)") (class "Default")
      (node (ref "U6") (pin "7") (pinfunction "FSR_7") (pintype "input"))
    )
    (net (code "62") (name "unconnected-(U6-GAIN-Pad13)") (class "Default")
      (node (ref "U6") (pin "13") (pinfunction "GAIN_13") (pintype "passive"))
    )
    (net (code "63") (name "unconnected-(U6-NC-Pad15)") (class "Default")
      (node (ref "U6") (pin "15") (pinfunction "NC_15") (pintype "no_connect"))
    )
    (net (code "64") (name "unconnected-(U6-NC_2-Pad1)") (class "Default")
      (node (ref "U6") (pin "1") (pinfunction "NC_2_1") (pintype "no_connect"))
    )
    (net (code "65") (name "unconnected-(U6-NC_3-Pad5)") (class "Default")
      (node (ref "U6") (pin "5") (pinfunction "NC_3_5") (pintype "no_connect"))
    )
    (net (code "66") (name "unconnected-(U6-NC_4-Pad10)") (class "Default")
      (node (ref "U6") (pin "10") (pinfunction "NC_4_10") (pintype "no_connect"))
    )
    (net (code "67") (name "unconnected-(X1N-1-Pad21)") (class "Default")
      (node (ref "X1") (pin "21") (pinfunction "1_21") (pintype "passive"))
    )
    (net (code "68") (name "unconnected-(X1O-1-Pad22)") (class "Default")
      (node (ref "X1") (pin "22") (pinfunction "1_22") (pintype "passive"))
    )
  )
)
